# Processor.net
KiCad netlist of a schematic drawn in Altium Designer
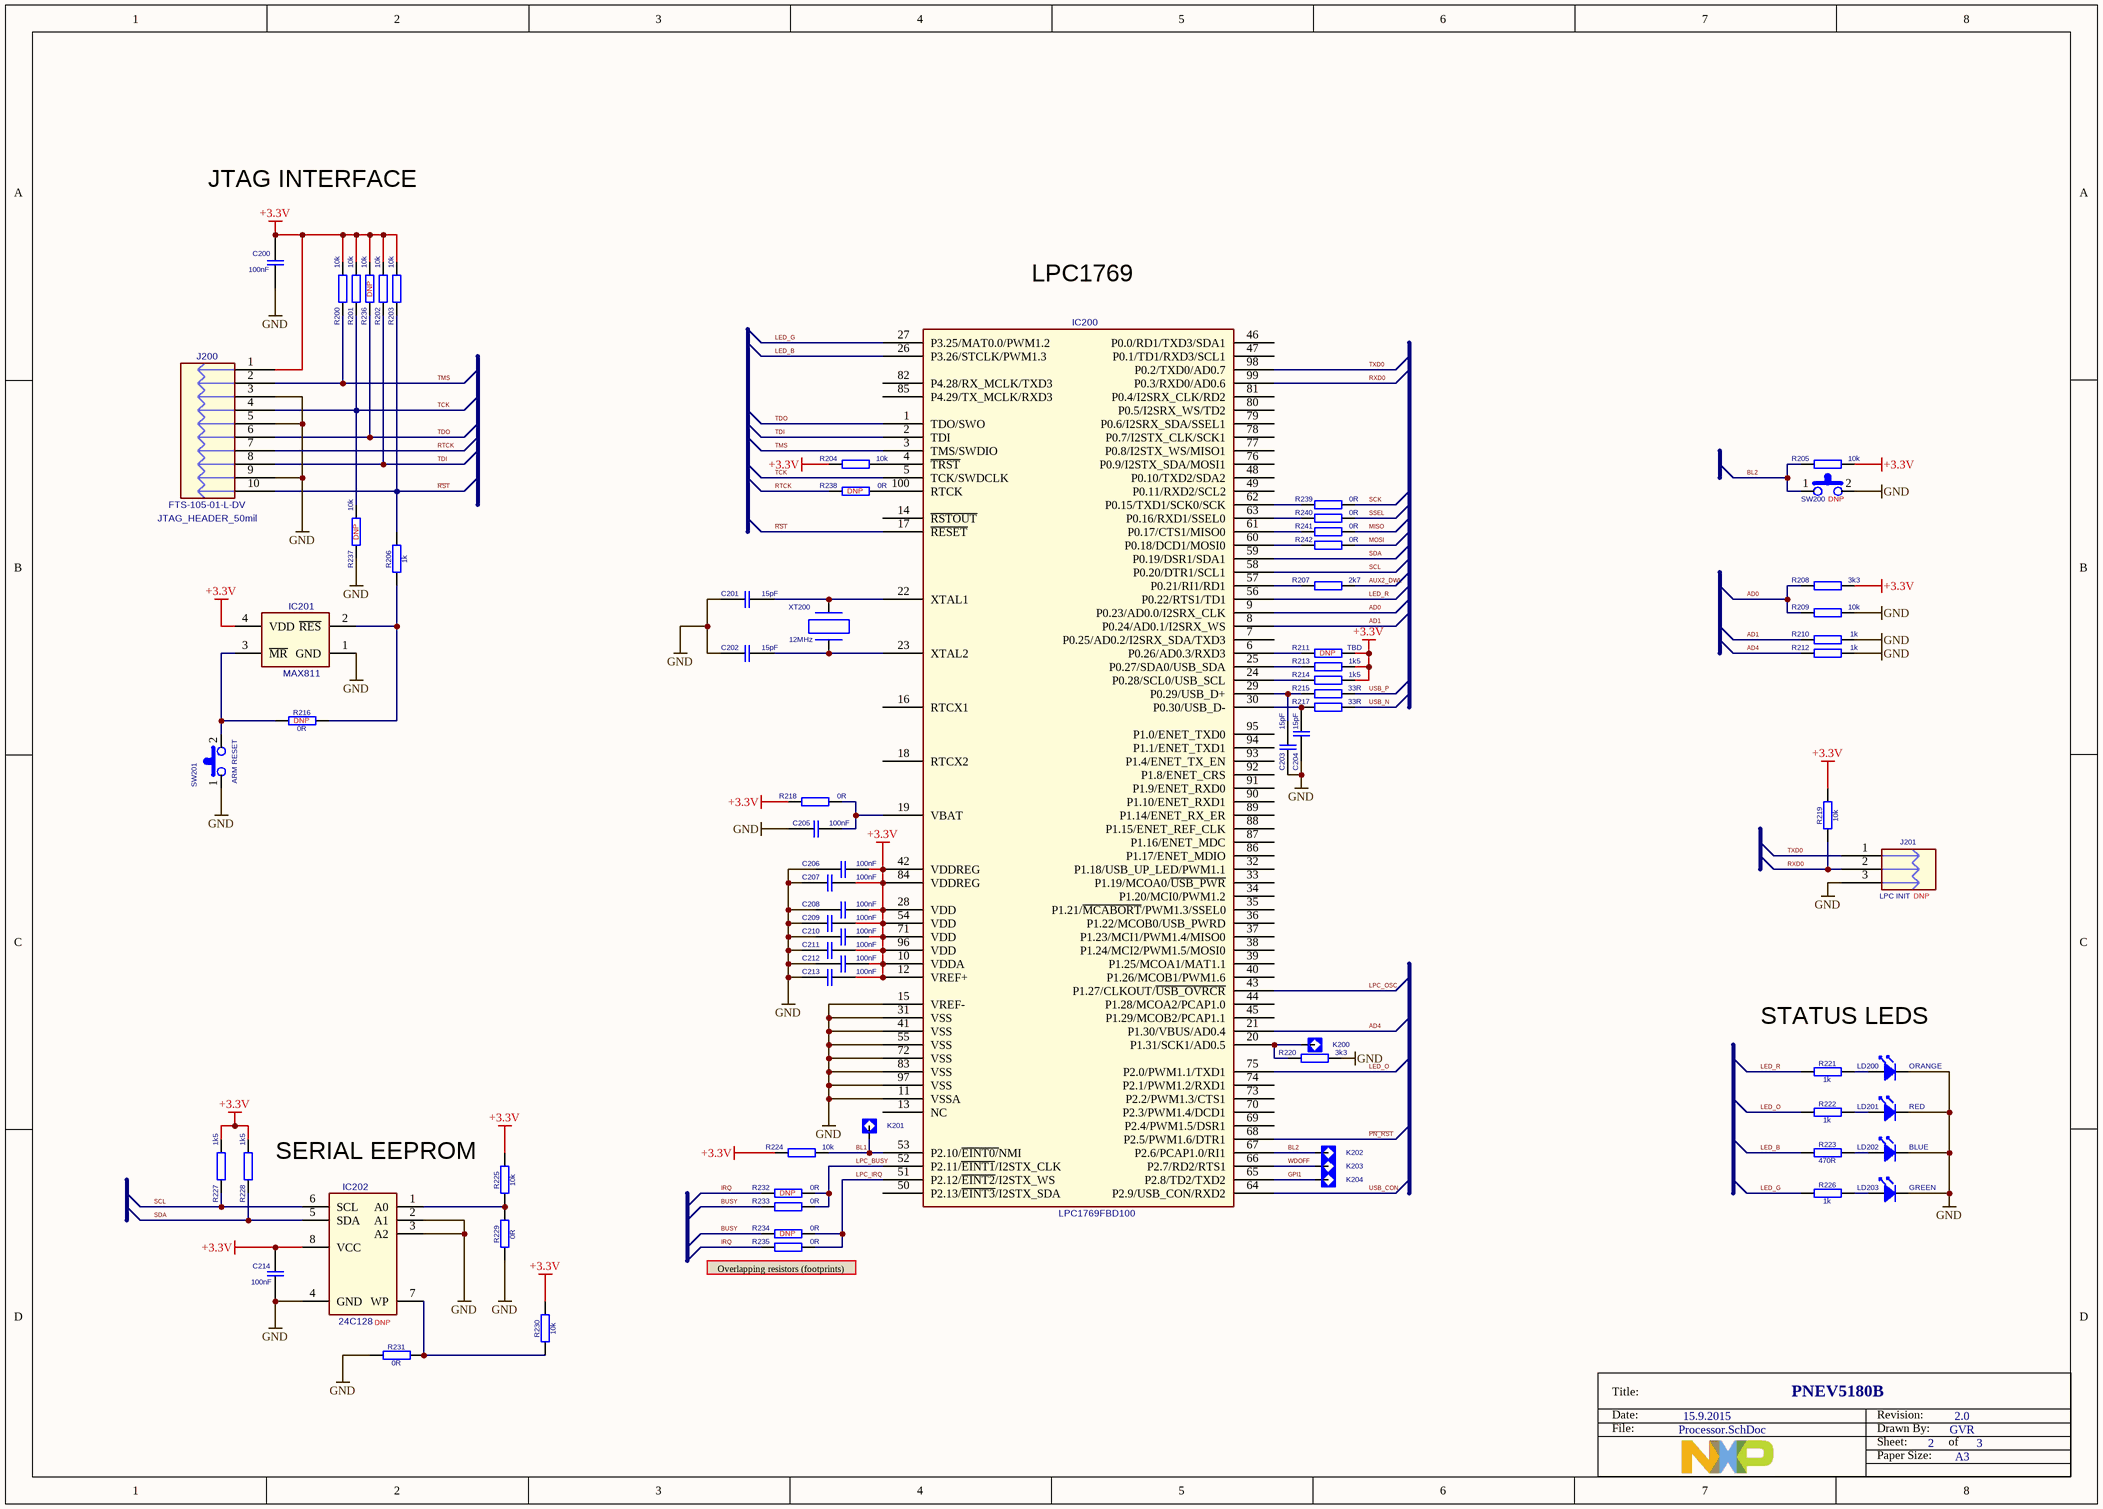
[diagram p0: Processor.SchDoc]

(export (version "E")
  (design (tool "Eeschema 10.0.6"))
  (components
    (comp (ref "C200")
      (value "100nF")
      (footprint "Y0603")
      (description "CAPC0603")
      (libsource (lib "ALT_CP") (part "CAPC0603"))
    )
    (comp (ref "C201")
      (value "15pF")
      (footprint "Y0603")
      (description "CAPC0603")
      (libsource (lib "ALT_CP") (part "CAPC0603"))
    )
    (comp (ref "C202")
      (value "15pF")
      (footprint "Y0603")
      (description "CAPC0603")
      (libsource (lib "ALT_CP") (part "CAPC0603"))
    )
    (comp (ref "C203")
      (value "15pF")
      (footprint "Y0603")
      (description "CAPC0603")
      (libsource (lib "ALT_CP") (part "CAPC0603"))
    )
    (comp (ref "C204")
      (value "15pF")
      (footprint "Y0603")
      (description "CAPC0603")
      (libsource (lib "ALT_CP") (part "CAPC0603"))
    )
    (comp (ref "C205")
      (value "100nF")
      (footprint "ALT_CP:Y0402")
      (description "CAPC0402")
      (libsource (lib "ALT_CP") (part "CAPC0402"))
    )
    (comp (ref "C206")
      (value "100nF")
      (footprint "ALT_CP:Y0402")
      (description "CAPC0402")
      (libsource (lib "ALT_CP") (part "CAPC0402"))
    )
    (comp (ref "C207")
      (value "100nF")
      (footprint "ALT_CP:Y0402")
      (description "CAPC0402")
      (libsource (lib "ALT_CP") (part "CAPC0402"))
    )
    (comp (ref "C208")
      (value "100nF")
      (footprint "ALT_CP:Y0402")
      (description "CAPC0402")
      (libsource (lib "ALT_CP") (part "CAPC0402"))
    )
    (comp (ref "C209")
      (value "100nF")
      (footprint "ALT_CP:Y0402")
      (description "CAPC0402")
      (libsource (lib "ALT_CP") (part "CAPC0402"))
    )
    (comp (ref "C210")
      (value "100nF")
      (footprint "ALT_CP:Y0402")
      (description "CAPC0402")
      (libsource (lib "ALT_CP") (part "CAPC0402"))
    )
    (comp (ref "C211")
      (value "100nF")
      (footprint "ALT_CP:Y0402")
      (description "CAPC0402")
      (libsource (lib "ALT_CP") (part "CAPC0402"))
    )
    (comp (ref "C212")
      (value "100nF")
      (footprint "ALT_CP:Y0402")
      (description "CAPC0402")
      (libsource (lib "ALT_CP") (part "CAPC0402"))
    )
    (comp (ref "C213")
      (value "100nF")
      (footprint "ALT_CP:Y0402")
      (description "CAPC0402")
      (libsource (lib "ALT_CP") (part "CAPC0402"))
    )
    (comp (ref "C214")
      (value "100nF")
      (footprint "Y0603")
      (description "CAPC0603")
      (libsource (lib "ALT_CP") (part "CAPC0603"))
    )
    (comp (ref "IC200")
      (value "LPC1769FBD100")
      (footprint "ALT_CP:TSQFP50P1600X1600X160-100N")
      (description "LQFP100")
      (libsource (lib "ALT_CP") (part "LPC176XFBD100"))
    )
    (comp (ref "IC201") (value "MAX811") (footprint "SOT143B") (libsource (lib "ALT_CP") (part "MAX811")))
    (comp (ref "IC202")
      (value "24C128")
      (footprint "ALT_CP:SOIC8")
      (description "SERIAL EEPROM")
      (fields (field (name "DNP") "DNP") (field (name "Comment") "24C128 DNP"))
      (libsource (lib "ALT_CP") (part "24CXX"))
    )
    (comp (ref "J200")
      (value "FTS-105-01-L-DV")
      (footprint "ALT_CP:CON_FTS-105-01-L-DV")
      (description "50mil, 2x5 pin (M), SMD")
      (fields (field (name "ALTIUM_UNNAMED_1") "JTAG_HEADER_50mil"))
      (libsource (lib "ALT_CP") (part "CON_JTAG_PINS"))
    )
    (comp (ref "J201")
      (value "LPC INIT")
      (footprint "ALT_CP:CON3M-LINE")
      (description "CON3M_LINE")
      (fields (field (name "DNP") "DNP") (field (name "Comment") "LPC INIT DNP"))
      (libsource (lib "ALT_CP") (part "CON3M_LINE"))
    )
    (comp (ref "K200")
      (value "TP1")
      (footprint "ALT_CP:TESTP_ROUND_1.0mm")
      (libsource (lib "ALT_CP") (part "TP1"))
    )
    (comp (ref "K201")
      (value "TP1")
      (footprint "ALT_CP:TESTP_ROUND_1.0mm")
      (libsource (lib "ALT_CP") (part "TP1"))
    )
    (comp (ref "K202")
      (value "TP1")
      (footprint "ALT_CP:TESTP_ROUND_1.0mm")
      (libsource (lib "ALT_CP") (part "TP1"))
    )
    (comp (ref "K203")
      (value "TP1")
      (footprint "ALT_CP:TESTP_ROUND_1.0mm")
      (libsource (lib "ALT_CP") (part "TP1"))
    )
    (comp (ref "K204")
      (value "TP1")
      (footprint "ALT_CP:TESTP_ROUND_1.0mm")
      (libsource (lib "ALT_CP") (part "TP1"))
    )
    (comp (ref "LD200")
      (value "ORANGE")
      (footprint "ALT_CP:LED_0603")
      (description "LEDY0603")
      (libsource (lib "ALT_CP") (part "LEDY0603"))
    )
    (comp (ref "LD201")
      (value "RED")
      (footprint "ALT_CP:LED_0603")
      (description "LEDY0603")
      (libsource (lib "ALT_CP") (part "LEDY0603"))
    )
    (comp (ref "LD202")
      (value "BLUE")
      (footprint "ALT_CP:LED_0603")
      (description "LEDY0603")
      (libsource (lib "ALT_CP") (part "LEDY0603"))
    )
    (comp (ref "LD203")
      (value "GREEN")
      (footprint "ALT_CP:LED_0603")
      (description "LEDY0603")
      (libsource (lib "ALT_CP") (part "LEDY0603"))
    )
    (comp (ref "R200")
      (value "10k")
      (footprint "Y0603")
      (description "RESC0603")
      (libsource (lib "ALT_CP") (part "RESC0603"))
    )
    (comp (ref "R201")
      (value "10k")
      (footprint "Y0603")
      (description "RESC0603")
      (libsource (lib "ALT_CP") (part "RESC0603"))
    )
    (comp (ref "R202")
      (value "10k")
      (footprint "Y0603")
      (description "RESC0603")
      (libsource (lib "ALT_CP") (part "RESC0603"))
    )
    (comp (ref "R203")
      (value "10k")
      (footprint "Y0603")
      (description "RESC0603")
      (libsource (lib "ALT_CP") (part "RESC0603"))
    )
    (comp (ref "R204")
      (value "10k")
      (footprint "Y0603")
      (description "RESC0603")
      (libsource (lib "ALT_CP") (part "RESC0603"))
    )
    (comp (ref "R205")
      (value "10k")
      (footprint "Y0603")
      (description "RESC0603")
      (libsource (lib "ALT_CP") (part "RESC0603"))
    )
    (comp (ref "R206")
      (value "1k")
      (footprint "Y0603")
      (description "RESC0603")
      (libsource (lib "ALT_CP") (part "RESC0603"))
    )
    (comp (ref "R207")
      (value "2k7")
      (footprint "Y0603")
      (description "RESC0603")
      (libsource (lib "ALT_CP") (part "RESC0603"))
    )
    (comp (ref "R208")
      (value "3k3")
      (footprint "Y0603")
      (description "RESC0603")
      (libsource (lib "ALT_CP") (part "RESC0603"))
    )
    (comp (ref "R209")
      (value "10k")
      (footprint "Y0603")
      (description "RESC0603")
      (libsource (lib "ALT_CP") (part "RESC0603"))
    )
    (comp (ref "R210")
      (value "1k")
      (footprint "Y0603")
      (description "RESC0603")
      (libsource (lib "ALT_CP") (part "RESC0603"))
    )
    (comp (ref "R211")
      (value "TBD")
      (footprint "Y0603")
      (description "RESC0603")
      (fields (field (name "DNP") "DNP") (field (name "Comment") "TBD DNP"))
      (libsource (lib "ALT_CP") (part "RESC0603"))
    )
    (comp (ref "R212")
      (value "1k")
      (footprint "Y0603")
      (description "RESC0603")
      (libsource (lib "ALT_CP") (part "RESC0603"))
    )
    (comp (ref "R213")
      (value "1k5")
      (footprint "Y0603")
      (description "RESC0603")
      (libsource (lib "ALT_CP") (part "RESC0603"))
    )
    (comp (ref "R214")
      (value "1k5")
      (footprint "Y0603")
      (description "RESC0603")
      (libsource (lib "ALT_CP") (part "RESC0603"))
    )
    (comp (ref "R215")
      (value "33R")
      (footprint "Y0603")
      (description "RESC0603")
      (libsource (lib "ALT_CP") (part "RESC0603"))
    )
    (comp (ref "R216")
      (value "0R")
      (footprint "Y0603")
      (description "RESC0603")
      (fields (field (name "DNP") "DNP") (field (name "Comment") "0R DNP"))
      (libsource (lib "ALT_CP") (part "RESC0603"))
    )
    (comp (ref "R217")
      (value "33R")
      (footprint "Y0603")
      (description "RESC0603")
      (libsource (lib "ALT_CP") (part "RESC0603"))
    )
    (comp (ref "R218")
      (value "0R")
      (footprint "Y0603")
      (description "RESC0603")
      (libsource (lib "ALT_CP") (part "RESC0603"))
    )
    (comp (ref "R219")
      (value "10k")
      (footprint "Y0603")
      (description "RESC0603")
      (libsource (lib "ALT_CP") (part "RESC0603"))
    )
    (comp (ref "R220")
      (value "3k3")
      (footprint "Y0603")
      (description "RESC0603")
      (libsource (lib "ALT_CP") (part "RESC0603"))
    )
    (comp (ref "R221")
      (value "1k")
      (footprint "Y0603")
      (description "RESC0603")
      (libsource (lib "ALT_CP") (part "RESC0603"))
    )
    (comp (ref "R222")
      (value "1k")
      (footprint "Y0603")
      (description "RESC0603")
      (libsource (lib "ALT_CP") (part "RESC0603"))
    )
    (comp (ref "R223")
      (value "470R")
      (footprint "Y0603")
      (description "RESC0603")
      (libsource (lib "ALT_CP") (part "RESC0603"))
    )
    (comp (ref "R224")
      (value "10k")
      (footprint "Y0603")
      (description "RESC0603")
      (libsource (lib "ALT_CP") (part "RESC0603"))
    )
    (comp (ref "R225")
      (value "10k")
      (footprint "Y0603")
      (description "RESC0603")
      (libsource (lib "ALT_CP") (part "RESC0603"))
    )
    (comp (ref "R226")
      (value "1k")
      (footprint "Y0603")
      (description "RESC0603")
      (libsource (lib "ALT_CP") (part "RESC0603"))
    )
    (comp (ref "R227")
      (value "1k5")
      (footprint "Y0603")
      (description "RESC0603")
      (libsource (lib "ALT_CP") (part "RESC0603"))
    )
    (comp (ref "R228")
      (value "1k5")
      (footprint "Y0603")
      (description "RESC0603")
      (libsource (lib "ALT_CP") (part "RESC0603"))
    )
    (comp (ref "R229")
      (value "0R")
      (footprint "Y0603")
      (description "RESC0603")
      (libsource (lib "ALT_CP") (part "RESC0603"))
    )
    (comp (ref "R230")
      (value "10k")
      (footprint "Y0603")
      (description "RESC0603")
      (libsource (lib "ALT_CP") (part "RESC0603"))
    )
    (comp (ref "R231")
      (value "0R")
      (footprint "Y0603")
      (description "RESC0603")
      (libsource (lib "ALT_CP") (part "RESC0603"))
    )
    (comp (ref "R232")
      (value "0R")
      (footprint "Y0805")
      (description "RESC0805")
      (fields (field (name "DNP") "DNP") (field (name "Comment") "0R DNP"))
      (libsource (lib "ALT_CP") (part "RESC0805"))
    )
    (comp (ref "R233")
      (value "0R")
      (footprint "Y0805")
      (description "RESC0805")
      (libsource (lib "ALT_CP") (part "RESC0805"))
    )
    (comp (ref "R234")
      (value "0R")
      (footprint "Y0805")
      (description "RESC0805")
      (fields (field (name "DNP") "DNP") (field (name "Comment") "0R DNP"))
      (libsource (lib "ALT_CP") (part "RESC0805"))
    )
    (comp (ref "R235")
      (value "0R")
      (footprint "Y0805")
      (description "RESC0805")
      (libsource (lib "ALT_CP") (part "RESC0805"))
    )
    (comp (ref "R236")
      (value "10k")
      (footprint "Y0603")
      (description "RESC0603")
      (fields (field (name "DNP") "DNP") (field (name "Comment") "10k DNP"))
      (libsource (lib "ALT_CP") (part "RESC0603"))
    )
    (comp (ref "R237")
      (value "10k")
      (footprint "Y0603")
      (description "RESC0603")
      (fields (field (name "DNP") "DNP") (field (name "Comment") "10k DNP"))
      (libsource (lib "ALT_CP") (part "RESC0603"))
    )
    (comp (ref "R238")
      (value "0R")
      (footprint "Y0603")
      (description "RESC0603")
      (fields (field (name "DNP") "DNP") (field (name "Comment") "0R DNP"))
      (libsource (lib "ALT_CP") (part "RESC0603"))
    )
    (comp (ref "R239")
      (value "0R")
      (footprint "ALT_CP:Y0402")
      (description "RESC0402")
      (libsource (lib "ALT_CP") (part "RESC0402"))
    )
    (comp (ref "R240")
      (value "0R")
      (footprint "ALT_CP:Y0402")
      (description "RESC0402")
      (libsource (lib "ALT_CP") (part "RESC0402"))
    )
    (comp (ref "R241")
      (value "0R")
      (footprint "ALT_CP:Y0402")
      (description "RESC0402")
      (libsource (lib "ALT_CP") (part "RESC0402"))
    )
    (comp (ref "R242")
      (value "0R")
      (footprint "ALT_CP:Y0402")
      (description "RESC0402")
      (libsource (lib "ALT_CP") (part "RESC0402"))
    )
    (comp (ref "SW200")
      (value "DTSM-32S-B DNP")
      (footprint "ALT_CP:SW_DTSM-32S-B")
      (description "DTSM-32S-B")
      (fields (field (name "DNP") "DNP"))
      (libsource (lib "ALT_CP") (part "SWITCH_SMD"))
    )
    (comp (ref "SW201")
      (value "DTSM-32S-B")
      (footprint "ALT_CP:SW_DTSM-32S-B")
      (fields (field (name "ALTIUM_UNNAMED_1") "ARM RESET"))
      (libsource (lib "ALT_CP") (part "SWITCH_SMD"))
    )
    (comp (ref "XT200")
      (value "12MHz")
      (footprint "ALT_CP:QUARTZ_NX5032GA")
      (description "QUARTZ_NX5032")
      (libsource (lib "ALT_CP") (part "QUARTZ_NX5032"))
    )
  )
  (nets
    (net (code "1") (name "+3.3V") (class "Default")
      (node (ref "C200") (pin "1") (pintype "passive"))
      (node (ref "C206") (pin "2") (pintype "passive"))
      (node (ref "C207") (pin "2") (pintype "passive"))
      (node (ref "C208") (pin "2") (pintype "passive"))
      (node (ref "C209") (pin "2") (pintype "passive"))
      (node (ref "C210") (pin "2") (pintype "passive"))
      (node (ref "C211") (pin "2") (pintype "passive"))
      (node (ref "C212") (pin "2") (pintype "passive"))
      (node (ref "C213") (pin "2") (pintype "passive"))
      (node (ref "C214") (pin "2") (pintype "passive"))
      (node (ref "IC200") (pin "10") (pinfunction "VDDA_10") (pintype "passive"))
      (node (ref "IC200") (pin "12") (pinfunction "VREF+_12") (pintype "passive"))
      (node (ref "IC200") (pin "28") (pinfunction "VDD_28") (pintype "passive"))
      (node (ref "IC200") (pin "42") (pinfunction "VDDREG_42") (pintype "passive"))
      (node (ref "IC200") (pin "54") (pinfunction "VDD_54") (pintype "passive"))
      (node (ref "IC200") (pin "71") (pinfunction "VDD_71") (pintype "passive"))
      (node (ref "IC200") (pin "84") (pinfunction "VDDREG_84") (pintype "passive"))
      (node (ref "IC200") (pin "96") (pinfunction "VDD_96") (pintype "passive"))
      (node (ref "IC201") (pin "4") (pinfunction "VDD_4") (pintype "passive"))
      (node (ref "IC202") (pin "8") (pinfunction "VCC_8") (pintype "passive"))
      (node (ref "J200") (pin "1") (pintype "passive"))
      (node (ref "R200") (pin "2") (pintype "passive"))
      (node (ref "R201") (pin "2") (pintype "passive"))
      (node (ref "R202") (pin "2") (pintype "passive"))
      (node (ref "R203") (pin "2") (pintype "passive"))
      (node (ref "R204") (pin "2") (pintype "passive"))
      (node (ref "R205") (pin "1") (pintype "passive"))
      (node (ref "R208") (pin "1") (pintype "passive"))
      (node (ref "R211") (pin "1") (pintype "passive"))
      (node (ref "R213") (pin "1") (pintype "passive"))
      (node (ref "R214") (pin "1") (pintype "passive"))
      (node (ref "R218") (pin "2") (pintype "passive"))
      (node (ref "R219") (pin "2") (pintype "passive"))
      (node (ref "R224") (pin "2") (pintype "passive"))
      (node (ref "R225") (pin "1") (pintype "passive"))
      (node (ref "R227") (pin "1") (pintype "passive"))
      (node (ref "R228") (pin "1") (pintype "passive"))
      (node (ref "R230") (pin "1") (pintype "passive"))
      (node (ref "R236") (pin "2") (pintype "passive"))
    )
    (net (code "2") (name "/AD0") (class "Default")
      (node (ref "IC200") (pin "9") (pinfunction "P0.23/AD0.0/I2SRX_CLK_9") (pintype "passive"))
      (node (ref "R208") (pin "2") (pintype "passive"))
      (node (ref "R209") (pin "2") (pintype "passive"))
    )
    (net (code "3") (name "/AD1") (class "Default")
      (node (ref "IC200") (pin "8") (pinfunction "P0.24/AD0.1/I2SRX_WS_8") (pintype "passive"))
      (node (ref "R210") (pin "2") (pintype "passive"))
    )
    (net (code "4") (name "/AD4") (class "Default")
      (node (ref "IC200") (pin "21") (pinfunction "P1.30/VBUS/AD0.4_21") (pintype "passive"))
      (node (ref "R212") (pin "2") (pintype "passive"))
    )
    (net (code "5") (name "/AUX2_DWL") (class "Default") (node (ref "R207") (pin "1") (pintype "passive")))
    (net (code "6") (name "/BL1") (class "Default")
      (node (ref "IC200") (pin "53") (pinfunction "P2.10/~{EINT0/}NMI_53") (pintype "passive"))
      (node (ref "K201") (pin "1") (pintype "passive"))
      (node (ref "R224") (pin "1") (pintype "passive"))
    )
    (net (code "7") (name "/BL2") (class "Default")
      (node (ref "IC200") (pin "67") (pinfunction "P2.6/PCAP1.0/RI1_67") (pintype "passive"))
      (node (ref "K202") (pin "1") (pintype "passive"))
      (node (ref "R205") (pin "2") (pintype "passive"))
      (node (ref "SW200") (pin "1") (pinfunction "1_1") (pintype "passive"))
    )
    (net (code "8") (name "/BUSY") (class "Default")
      (node (ref "R233") (pin "1") (pintype "passive"))
      (node (ref "R234") (pin "1") (pintype "passive"))
    )
    (net (code "9") (name "/GPI1") (class "Default")
      (node (ref "IC200") (pin "65") (pinfunction "P2.8/TD2/TXD2_65") (pintype "passive"))
      (node (ref "K204") (pin "1") (pintype "passive"))
    )
    (net (code "10") (name "/IRQ") (class "Default")
      (node (ref "R232") (pin "1") (pintype "passive"))
      (node (ref "R235") (pin "1") (pintype "passive"))
    )
    (net (code "11") (name "/LED_B") (class "Default")
      (node (ref "IC200") (pin "26") (pinfunction "P3.26/STCLK/PWM1.3_26") (pintype "passive"))
      (node (ref "R223") (pin "1") (pintype "passive"))
    )
    (net (code "12") (name "/LED_G") (class "Default")
      (node (ref "IC200") (pin "27") (pinfunction "P3.25/MAT0.0/PWM1.2_27") (pintype "passive"))
      (node (ref "R226") (pin "1") (pintype "passive"))
    )
    (net (code "13") (name "/LED_O") (class "Default")
      (node (ref "IC200") (pin "75") (pinfunction "P2.0/PWM1.1/TXD1_75") (pintype "passive"))
      (node (ref "R222") (pin "1") (pintype "passive"))
    )
    (net (code "14") (name "/LED_R") (class "Default")
      (node (ref "IC200") (pin "56") (pinfunction "P0.22/RTS1/TD1_56") (pintype "passive"))
      (node (ref "R221") (pin "1") (pintype "passive"))
    )
    (net (code "15") (name "/LPC_BUSY") (class "Default")
      (node (ref "IC200") (pin "52") (pinfunction "P2.11/~{EINT1}/I2STX_CLK_52") (pintype "passive"))
      (node (ref "R232") (pin "2") (pintype "passive"))
      (node (ref "R233") (pin "2") (pintype "passive"))
    )
    (net (code "16") (name "/LPC_IRQ") (class "Default")
      (node (ref "IC200") (pin "51") (pinfunction "P2.12/~{EINT2}/I2STX_WS_51") (pintype "passive"))
      (node (ref "R234") (pin "2") (pintype "passive"))
      (node (ref "R235") (pin "2") (pintype "passive"))
    )
    (net (code "17") (name "/LPC_OSC") (class "Default")
      (node (ref "IC200") (pin "43") (pinfunction "P1.27/CLKOUT/~{USB_OVRCR}_43") (pintype "passive"))
    )
    (net (code "18") (name "/MISO") (class "Default") (node (ref "R241") (pin "1") (pintype "passive")))
    (net (code "19") (name "/MOSI") (class "Default") (node (ref "R242") (pin "1") (pintype "passive")))
    (net (code "20") (name "/RTCK") (class "Default")
      (node (ref "J200") (pin "7") (pintype "passive"))
      (node (ref "R238") (pin "2") (pintype "passive"))
    )
    (net (code "21") (name "/RXD0") (class "Default")
      (node (ref "IC200") (pin "99") (pinfunction "P0.3/RXD0/AD0.6_99") (pintype "passive"))
      (node (ref "J201") (pin "2") (pinfunction "P2_2") (pintype "passive"))
      (node (ref "R219") (pin "1") (pintype "passive"))
    )
    (net (code "22") (name "/SCK") (class "Default") (node (ref "R239") (pin "1") (pintype "passive")))
    (net (code "23") (name "/SCL") (class "Default")
      (node (ref "IC200") (pin "58") (pinfunction "P0.20/DTR1/SCL1_58") (pintype "passive"))
      (node (ref "IC202") (pin "6") (pinfunction "SCL_6") (pintype "passive"))
      (node (ref "R227") (pin "2") (pintype "passive"))
    )
    (net (code "24") (name "/SDA") (class "Default")
      (node (ref "IC200") (pin "59") (pinfunction "P0.19/DSR1/SDA1_59") (pintype "passive"))
      (node (ref "IC202") (pin "5") (pinfunction "SDA_5") (pintype "passive"))
      (node (ref "R228") (pin "2") (pintype "passive"))
    )
    (net (code "25") (name "/SSEL") (class "Default") (node (ref "R240") (pin "1") (pintype "passive")))
    (net (code "26") (name "/TCK") (class "Default")
      (node (ref "IC200") (pin "5") (pinfunction "TCK/SWDCLK_5") (pintype "passive"))
      (node (ref "J200") (pin "4") (pintype "passive"))
      (node (ref "R201") (pin "1") (pintype "passive"))
      (node (ref "R237") (pin "2") (pintype "passive"))
    )
    (net (code "27") (name "/TDI") (class "Default")
      (node (ref "IC200") (pin "2") (pinfunction "TDI_2") (pintype "passive"))
      (node (ref "J200") (pin "8") (pintype "passive"))
      (node (ref "R202") (pin "1") (pintype "passive"))
    )
    (net (code "28") (name "/TDO") (class "Default")
      (node (ref "IC200") (pin "1") (pinfunction "TDO/SWO_1") (pintype "passive"))
      (node (ref "J200") (pin "6") (pintype "passive"))
      (node (ref "R236") (pin "1") (pintype "passive"))
    )
    (net (code "29") (name "/TMS") (class "Default")
      (node (ref "IC200") (pin "3") (pinfunction "TMS/SWDIO_3") (pintype "passive"))
      (node (ref "J200") (pin "2") (pintype "passive"))
      (node (ref "R200") (pin "1") (pintype "passive"))
    )
    (net (code "30") (name "/TXD0") (class "Default")
      (node (ref "IC200") (pin "98") (pinfunction "P0.2/TXD0/AD0.7_98") (pintype "passive"))
      (node (ref "J201") (pin "1") (pinfunction "P1_1") (pintype "passive"))
    )
    (net (code "31") (name "/USB_CON") (class "Default")
      (node (ref "IC200") (pin "64") (pinfunction "P2.9/USB_CON/RXD2_64") (pintype "passive"))
    )
    (net (code "32") (name "/USB_N") (class "Default") (node (ref "R217") (pin "1") (pintype "passive")))
    (net (code "33") (name "/USB_P") (class "Default") (node (ref "R215") (pin "1") (pintype "passive")))
    (net (code "34") (name "/WDOFF") (class "Default")
      (node (ref "IC200") (pin "66") (pinfunction "P2.7/RD2/RTS1_66") (pintype "passive"))
      (node (ref "K203") (pin "1") (pintype "passive"))
    )
    (net (code "35") (name "/~{PN_RST}") (class "Default")
      (node (ref "IC200") (pin "68") (pinfunction "P2.5/PWM1.6/DTR1_68") (pintype "passive"))
    )
    (net (code "36") (name "/~{RST}") (class "Default")
      (node (ref "IC200") (pin "17") (pinfunction "~{RESET}_17") (pintype "passive"))
      (node (ref "J200") (pin "10") (pintype "passive"))
      (node (ref "R203") (pin "1") (pintype "passive"))
      (node (ref "R206") (pin "2") (pintype "passive"))
    )
    (net (code "37") (name "GND") (class "Default")
      (node (ref "C200") (pin "2") (pintype "passive"))
      (node (ref "C201") (pin "2") (pintype "passive"))
      (node (ref "C202") (pin "2") (pintype "passive"))
      (node (ref "C203") (pin "1") (pintype "passive"))
      (node (ref "C204") (pin "1") (pintype "passive"))
      (node (ref "C205") (pin "1") (pintype "passive"))
      (node (ref "C206") (pin "1") (pintype "passive"))
      (node (ref "C207") (pin "1") (pintype "passive"))
      (node (ref "C208") (pin "1") (pintype "passive"))
      (node (ref "C209") (pin "1") (pintype "passive"))
      (node (ref "C210") (pin "1") (pintype "passive"))
      (node (ref "C211") (pin "1") (pintype "passive"))
      (node (ref "C212") (pin "1") (pintype "passive"))
      (node (ref "C213") (pin "1") (pintype "passive"))
      (node (ref "C214") (pin "1") (pintype "passive"))
      (node (ref "IC200") (pin "11") (pinfunction "VSSA_11") (pintype "passive"))
      (node (ref "IC200") (pin "15") (pinfunction "VREF-_15") (pintype "passive"))
      (node (ref "IC200") (pin "31") (pinfunction "VSS_31") (pintype "passive"))
      (node (ref "IC200") (pin "41") (pinfunction "VSS_41") (pintype "passive"))
      (node (ref "IC200") (pin "55") (pinfunction "VSS_55") (pintype "passive"))
      (node (ref "IC200") (pin "72") (pinfunction "VSS_72") (pintype "passive"))
      (node (ref "IC200") (pin "83") (pinfunction "VSS_83") (pintype "passive"))
      (node (ref "IC200") (pin "97") (pinfunction "VSS_97") (pintype "passive"))
      (node (ref "IC201") (pin "1") (pinfunction "GND_1") (pintype "passive"))
      (node (ref "IC202") (pin "2") (pinfunction "A1_2") (pintype "passive"))
      (node (ref "IC202") (pin "3") (pinfunction "A2_3") (pintype "passive"))
      (node (ref "IC202") (pin "4") (pinfunction "GND_4") (pintype "passive"))
      (node (ref "J200") (pin "3") (pintype "passive"))
      (node (ref "J200") (pin "5") (pintype "passive"))
      (node (ref "J200") (pin "9") (pintype "passive"))
      (node (ref "J201") (pin "3") (pinfunction "P3_3") (pintype "passive"))
      (node (ref "LD200") (pin "1") (pintype "passive"))
      (node (ref "LD201") (pin "1") (pintype "passive"))
      (node (ref "LD202") (pin "1") (pintype "passive"))
      (node (ref "LD203") (pin "1") (pintype "passive"))
      (node (ref "R209") (pin "1") (pintype "passive"))
      (node (ref "R210") (pin "1") (pintype "passive"))
      (node (ref "R212") (pin "1") (pintype "passive"))
      (node (ref "R220") (pin "1") (pintype "passive"))
      (node (ref "R229") (pin "2") (pintype "passive"))
      (node (ref "R231") (pin "2") (pintype "passive"))
      (node (ref "R237") (pin "1") (pintype "passive"))
      (node (ref "SW200") (pin "2") (pinfunction "2_2") (pintype "passive"))
      (node (ref "SW201") (pin "1") (pinfunction "1_1") (pintype "passive"))
    )
    (net (code "38") (name "Net-(IC200-P0.15{slash}TXD1{slash}SCK0{slash}SCK)") (class "Default")
      (node (ref "IC200") (pin "62") (pinfunction "P0.15/TXD1/SCK0/SCK_62") (pintype "passive"))
      (node (ref "R239") (pin "2") (pintype "passive"))
    )
    (net (code "39") (name "Net-(IC200-P0.16{slash}RXD1{slash}SSEL0)") (class "Default")
      (node (ref "IC200") (pin "63") (pinfunction "P0.16/RXD1/SSEL0_63") (pintype "passive"))
      (node (ref "R240") (pin "2") (pintype "passive"))
    )
    (net (code "40") (name "Net-(IC200-P0.17{slash}CTS1{slash}MISO0)") (class "Default")
      (node (ref "IC200") (pin "61") (pinfunction "P0.17/CTS1/MISO0_61") (pintype "passive"))
      (node (ref "R241") (pin "2") (pintype "passive"))
    )
    (net (code "41") (name "Net-(IC200-P0.18{slash}DCD1{slash}MOSI0)") (class "Default")
      (node (ref "IC200") (pin "60") (pinfunction "P0.18/DCD1/MOSI0_60") (pintype "passive"))
      (node (ref "R242") (pin "2") (pintype "passive"))
    )
    (net (code "42") (name "Net-(IC200-P0.21{slash}RI1{slash}RD1)") (class "Default")
      (node (ref "IC200") (pin "57") (pinfunction "P0.21/RI1/RD1_57") (pintype "passive"))
      (node (ref "R207") (pin "2") (pintype "passive"))
    )
    (net (code "43") (name "Net-(IC200-P0.26{slash}AD0.3{slash}RXD3)") (class "Default")
      (node (ref "IC200") (pin "6") (pinfunction "P0.26/AD0.3/RXD3_6") (pintype "passive"))
      (node (ref "R211") (pin "2") (pintype "passive"))
    )
    (net (code "44") (name "Net-(IC200-P0.27{slash}SDA0{slash}USB_SDA)") (class "Default")
      (node (ref "IC200") (pin "25") (pinfunction "P0.27/SDA0/USB_SDA_25") (pintype "passive"))
      (node (ref "R213") (pin "2") (pintype "passive"))
    )
    (net (code "45") (name "Net-(IC200-P0.28{slash}SCL0{slash}USB_SCL)") (class "Default")
      (node (ref "IC200") (pin "24") (pinfunction "P0.28/SCL0/USB_SCL_24") (pintype "passive"))
      (node (ref "R214") (pin "2") (pintype "passive"))
    )
    (net (code "46") (name "Net-(IC200-P0.29{slash}USB_D+)") (class "Default")
      (node (ref "C203") (pin "2") (pintype "passive"))
      (node (ref "IC200") (pin "29") (pinfunction "P0.29/USB_D+_29") (pintype "passive"))
      (node (ref "R215") (pin "2") (pintype "passive"))
    )
    (net (code "47") (name "Net-(IC200-P0.30{slash}USB_D-)") (class "Default")
      (node (ref "C204") (pin "2") (pintype "passive"))
      (node (ref "IC200") (pin "30") (pinfunction "P0.30/USB_D-_30") (pintype "passive"))
      (node (ref "R217") (pin "2") (pintype "passive"))
    )
    (net (code "48") (name "Net-(IC200-P1.31{slash}SCK1{slash}AD0.5)") (class "Default")
      (node (ref "IC200") (pin "20") (pinfunction "P1.31/SCK1/AD0.5_20") (pintype "passive"))
      (node (ref "K200") (pin "1") (pintype "passive"))
      (node (ref "R220") (pin "2") (pintype "passive"))
    )
    (net (code "49") (name "Net-(IC200-RTCK)") (class "Default")
      (node (ref "IC200") (pin "100") (pinfunction "RTCK_100") (pintype "passive"))
      (node (ref "R238") (pin "1") (pintype "passive"))
    )
    (net (code "50") (name "Net-(IC200-VBAT)") (class "Default")
      (node (ref "C205") (pin "2") (pintype "passive"))
      (node (ref "IC200") (pin "19") (pinfunction "VBAT_19") (pintype "passive"))
      (node (ref "R218") (pin "1") (pintype "passive"))
    )
    (net (code "51") (name "Net-(IC200-XTAL1)") (class "Default")
      (node (ref "C201") (pin "1") (pintype "passive"))
      (node (ref "IC200") (pin "22") (pinfunction "XTAL1_22") (pintype "passive"))
      (node (ref "XT200") (pin "2") (pinfunction "2_2") (pintype "passive"))
    )
    (net (code "52") (name "Net-(IC200-XTAL2)") (class "Default")
      (node (ref "C202") (pin "1") (pintype "passive"))
      (node (ref "IC200") (pin "23") (pinfunction "XTAL2_23") (pintype "passive"))
      (node (ref "XT200") (pin "1") (pinfunction "1_1") (pintype "passive"))
    )
    (net (code "53") (name "Net-(IC200-~{TRST})") (class "Default")
      (node (ref "IC200") (pin "4") (pinfunction "~{TRST}_4") (pintype "passive"))
      (node (ref "R204") (pin "1") (pintype "passive"))
    )
    (net (code "54") (name "Net-(IC201-~{MR})") (class "Default")
      (node (ref "IC201") (pin "3") (pinfunction "~{MR}_3") (pintype "passive"))
      (node (ref "R216") (pin "1") (pintype "passive"))
      (node (ref "SW201") (pin "2") (pinfunction "2_2") (pintype "passive"))
    )
    (net (code "55") (name "Net-(IC201-~{RES})") (class "Default")
      (node (ref "IC201") (pin "2") (pinfunction "~{RES}_2") (pintype "passive"))
      (node (ref "R206") (pin "1") (pintype "passive"))
      (node (ref "R216") (pin "2") (pintype "passive"))
    )
    (net (code "56") (name "Net-(IC202-A0)") (class "Default")
      (node (ref "IC202") (pin "1") (pinfunction "A0_1") (pintype "passive"))
      (node (ref "R225") (pin "2") (pintype "passive"))
      (node (ref "R229") (pin "1") (pintype "passive"))
    )
    (net (code "57") (name "Net-(IC202-WP)") (class "Default")
      (node (ref "IC202") (pin "7") (pinfunction "WP_7") (pintype "passive"))
      (node (ref "R230") (pin "2") (pintype "passive"))
      (node (ref "R231") (pin "1") (pintype "passive"))
    )
    (net (code "58") (name "Net-(LD200-Pad2)") (class "Default")
      (node (ref "LD200") (pin "2") (pintype "passive"))
      (node (ref "R221") (pin "2") (pintype "passive"))
    )
    (net (code "59") (name "Net-(LD201-Pad2)") (class "Default")
      (node (ref "LD201") (pin "2") (pintype "passive"))
      (node (ref "R222") (pin "2") (pintype "passive"))
    )
    (net (code "60") (name "Net-(LD202-Pad2)") (class "Default")
      (node (ref "LD202") (pin "2") (pintype "passive"))
      (node (ref "R223") (pin "2") (pintype "passive"))
    )
    (net (code "61") (name "Net-(LD203-Pad2)") (class "Default")
      (node (ref "LD203") (pin "2") (pintype "passive"))
      (node (ref "R226") (pin "2") (pintype "passive"))
    )
    (net (code "62") (name "unconnected-(IC200-NC-Pad13)") (class "Default")
      (node (ref "IC200") (pin "13") (pinfunction "NC_13") (pintype "passive"))
    )
    (net (code "63") (name "unconnected-(IC200-P0.0{slash}RD1{slash}TXD3{slash}SDA1-Pad46)") (class "Default")
      (node (ref "IC200") (pin "46") (pinfunction "P0.0/RD1/TXD3/SDA1_46") (pintype "passive"))
    )
    (net (code "64") (name "unconnected-(IC200-P0.1{slash}TD1{slash}RXD3{slash}SCL1-Pad47)") (class "Default")
      (node (ref "IC200") (pin "47") (pinfunction "P0.1/TD1/RXD3/SCL1_47") (pintype "passive"))
    )
    (net (code "65") (name "unconnected-(IC200-P0.4{slash}I2SRX_CLK{slash}RD2-Pad81)") (class "Default")
      (node (ref "IC200") (pin "81") (pinfunction "P0.4/I2SRX_CLK/RD2_81") (pintype "passive"))
    )
    (net (code "66") (name "unconnected-(IC200-P0.5{slash}I2SRX_WS{slash}TD2-Pad80)") (class "Default")
      (node (ref "IC200") (pin "80") (pinfunction "P0.5/I2SRX_WS/TD2_80") (pintype "passive"))
    )
    (net (code "67") (name "unconnected-(IC200-P0.6{slash}I2SRX_SDA{slash}SSEL1-Pad79)") (class "Default")
      (node (ref "IC200") (pin "79") (pinfunction "P0.6/I2SRX_SDA/SSEL1_79") (pintype "passive"))
    )
    (net (code "68") (name "unconnected-(IC200-P0.7{slash}I2STX_CLK{slash}SCK1-Pad78)") (class "Default")
      (node (ref "IC200") (pin "78") (pinfunction "P0.7/I2STX_CLK/SCK1_78") (pintype "passive"))
    )
    (net (code "69") (name "unconnected-(IC200-P0.8{slash}I2STX_WS{slash}MISO1-Pad77)") (class "Default")
      (node (ref "IC200") (pin "77") (pinfunction "P0.8/I2STX_WS/MISO1_77") (pintype "passive"))
    )
    (net (code "70") (name "unconnected-(IC200-P0.9{slash}I2STX_SDA{slash}MOSI1-Pad76)") (class "Default")
      (node (ref "IC200") (pin "76") (pinfunction "P0.9/I2STX_SDA/MOSI1_76") (pintype "passive"))
    )
    (net (code "71") (name "unconnected-(IC200-P0.10{slash}TXD2{slash}SDA2-Pad48)") (class "Default")
      (node (ref "IC200") (pin "48") (pinfunction "P0.10/TXD2/SDA2_48") (pintype "passive"))
    )
    (net (code "72") (name "unconnected-(IC200-P0.11{slash}RXD2{slash}SCL2-Pad49)") (class "Default")
      (node (ref "IC200") (pin "49") (pinfunction "P0.11/RXD2/SCL2_49") (pintype "passive"))
    )
    (net (code "73") (name "unconnected-(IC200-P0.25{slash}AD0.2{slash}I2SRX_SDA{slash}TXD3-Pad7)") (class "Default")
      (node (ref "IC200") (pin "7") (pinfunction "P0.25/AD0.2/I2SRX_SDA/TXD3_7") (pintype "passive"))
    )
    (net (code "74") (name "unconnected-(IC200-P1.0{slash}ENET_TXD0-Pad95)") (class "Default")
      (node (ref "IC200") (pin "95") (pinfunction "P1.0/ENET_TXD0_95") (pintype "passive"))
    )
    (net (code "75") (name "unconnected-(IC200-P1.1{slash}ENET_TXD1-Pad94)") (class "Default")
      (node (ref "IC200") (pin "94") (pinfunction "P1.1/ENET_TXD1_94") (pintype "passive"))
    )
    (net (code "76") (name "unconnected-(IC200-P1.4{slash}ENET_TX_EN-Pad93)") (class "Default")
      (node (ref "IC200") (pin "93") (pinfunction "P1.4/ENET_TX_EN_93") (pintype "passive"))
    )
    (net (code "77") (name "unconnected-(IC200-P1.8{slash}ENET_CRS-Pad92)") (class "Default")
      (node (ref "IC200") (pin "92") (pinfunction "P1.8/ENET_CRS_92") (pintype "passive"))
    )
    (net (code "78") (name "unconnected-(IC200-P1.9{slash}ENET_RXD0-Pad91)") (class "Default")
      (node (ref "IC200") (pin "91") (pinfunction "P1.9/ENET_RXD0_91") (pintype "passive"))
    )
    (net (code "79") (name "unconnected-(IC200-P1.10{slash}ENET_RXD1-Pad90)") (class "Default")
      (node (ref "IC200") (pin "90") (pinfunction "P1.10/ENET_RXD1_90") (pintype "passive"))
    )
    (net (code "80") (name "unconnected-(IC200-P1.14{slash}ENET_RX_ER-Pad89)") (class "Default")
      (node (ref "IC200") (pin "89") (pinfunction "P1.14/ENET_RX_ER_89") (pintype "passive"))
    )
    (net (code "81") (name "unconnected-(IC200-P1.15{slash}ENET_REF_CLK-Pad88)") (class "Default")
      (node (ref "IC200") (pin "88") (pinfunction "P1.15/ENET_REF_CLK_88") (pintype "passive"))
    )
    (net (code "82") (name "unconnected-(IC200-P1.16{slash}ENET_MDC-Pad87)") (class "Default")
      (node (ref "IC200") (pin "87") (pinfunction "P1.16/ENET_MDC_87") (pintype "passive"))
    )
    (net (code "83") (name "unconnected-(IC200-P1.17{slash}ENET_MDIO-Pad86)") (class "Default")
      (node (ref "IC200") (pin "86") (pinfunction "P1.17/ENET_MDIO_86") (pintype "passive"))
    )
    (net (code "84") (name "unconnected-(IC200-P1.18{slash}USB_UP_LED{slash}PWM1.1-Pad32)") (class "Default")
      (node (ref "IC200") (pin "32") (pinfunction "P1.18/USB_UP_LED/PWM1.1_32") (pintype "passive"))
    )
    (net (code "85") (name "unconnected-(IC200-P1.19{slash}MCOA0{slash}~{USB_PWR}-Pad33)") (class "Default")
      (node (ref "IC200") (pin "33") (pinfunction "P1.19/MCOA0/~{USB_PWR}_33") (pintype "passive"))
    )
    (net (code "86") (name "unconnected-(IC200-P1.20{slash}MCI0{slash}PWM1.2-Pad34)") (class "Default")
      (node (ref "IC200") (pin "34") (pinfunction "P1.20/MCI0/PWM1.2_34") (pintype "passive"))
    )
    (net (code "87") (name "unconnected-(IC200-P1.21{slash}~{MCABORT}{slash}PWM1.3{slash}SSEL0-Pad35)") (class "Default")
      (node (ref "IC200") (pin "35") (pinfunction "P1.21/~{MCABORT}/PWM1.3/SSEL0_35") (pintype "passive"))
    )
    (net (code "88") (name "unconnected-(IC200-P1.22{slash}MCOB0{slash}USB_PWRD-Pad36)") (class "Default")
      (node (ref "IC200") (pin "36") (pinfunction "P1.22/MCOB0/USB_PWRD_36") (pintype "passive"))
    )
    (net (code "89") (name "unconnected-(IC200-P1.23{slash}MCI1{slash}PWM1.4{slash}MISO0-Pad37)") (class "Default")
      (node (ref "IC200") (pin "37") (pinfunction "P1.23/MCI1/PWM1.4/MISO0_37") (pintype "passive"))
    )
    (net (code "90") (name "unconnected-(IC200-P1.24{slash}MCI2{slash}PWM1.5{slash}MOSI0-Pad38)") (class "Default")
      (node (ref "IC200") (pin "38") (pinfunction "P1.24/MCI2/PWM1.5/MOSI0_38") (pintype "passive"))
    )
    (net (code "91") (name "unconnected-(IC200-P1.25{slash}MCOA1{slash}MAT1.1-Pad39)") (class "Default")
      (node (ref "IC200") (pin "39") (pinfunction "P1.25/MCOA1/MAT1.1_39") (pintype "passive"))
    )
    (net (code "92") (name "unconnected-(IC200-P1.26{slash}MCOB1{slash}PWM1.6-Pad40)") (class "Default")
      (node (ref "IC200") (pin "40") (pinfunction "P1.26/MCOB1/PWM1.6_40") (pintype "passive"))
    )
    (net (code "93") (name "unconnected-(IC200-P1.28{slash}MCOA2{slash}PCAP1.0-Pad44)") (class "Default")
      (node (ref "IC200") (pin "44") (pinfunction "P1.28/MCOA2/PCAP1.0_44") (pintype "passive"))
    )
    (net (code "94") (name "unconnected-(IC200-P1.29{slash}MCOB2{slash}PCAP1.1-Pad45)") (class "Default")
      (node (ref "IC200") (pin "45") (pinfunction "P1.29/MCOB2/PCAP1.1_45") (pintype "passive"))
    )
    (net (code "95") (name "unconnected-(IC200-P2.1{slash}PWM1.2{slash}RXD1-Pad74)") (class "Default")
      (node (ref "IC200") (pin "74") (pinfunction "P2.1/PWM1.2/RXD1_74") (pintype "passive"))
    )
    (net (code "96") (name "unconnected-(IC200-P2.2{slash}PWM1.3{slash}CTS1-Pad73)") (class "Default")
      (node (ref "IC200") (pin "73") (pinfunction "P2.2/PWM1.3/CTS1_73") (pintype "passive"))
    )
    (net (code "97") (name "unconnected-(IC200-P2.3{slash}PWM1.4{slash}DCD1-Pad70)") (class "Default")
      (node (ref "IC200") (pin "70") (pinfunction "P2.3/PWM1.4/DCD1_70") (pintype "passive"))
    )
    (net (code "98") (name "unconnected-(IC200-P2.4{slash}PWM1.5{slash}DSR1-Pad69)") (class "Default")
      (node (ref "IC200") (pin "69") (pinfunction "P2.4/PWM1.5/DSR1_69") (pintype "passive"))
    )
    (net (code "99") (name "unconnected-(IC200-P2.13{slash}~{EINT3}{slash}I2STX_SDA-Pad50)") (class "Default")
      (node (ref "IC200") (pin "50") (pinfunction "P2.13/~{EINT3}/I2STX_SDA_50") (pintype "passive"))
    )
    (net (code "100") (name "unconnected-(IC200-P4.28{slash}RX_MCLK{slash}TXD3-Pad82)") (class "Default")
      (node (ref "IC200") (pin "82") (pinfunction "P4.28/RX_MCLK/TXD3_82") (pintype "passive"))
    )
    (net (code "101") (name "unconnected-(IC200-P4.29{slash}TX_MCLK{slash}RXD3-Pad85)") (class "Default")
      (node (ref "IC200") (pin "85") (pinfunction "P4.29/TX_MCLK/RXD3_85") (pintype "passive"))
    )
    (net (code "102") (name "unconnected-(IC200-RTCX1-Pad16)") (class "Default")
      (node (ref "IC200") (pin "16") (pinfunction "RTCX1_16") (pintype "passive"))
    )
    (net (code "103") (name "unconnected-(IC200-RTCX2-Pad18)") (class "Default")
      (node (ref "IC200") (pin "18") (pinfunction "RTCX2_18") (pintype "passive"))
    )
    (net (code "104") (name "unconnected-(IC200-~{RSTOUT}-Pad14)") (class "Default")
      (node (ref "IC200") (pin "14") (pinfunction "~{RSTOUT}_14") (pintype "passive"))
    )
  )
)
